# Voltage_Regulator.net
KiCad netlist of a schematic drawn in Altium Designer
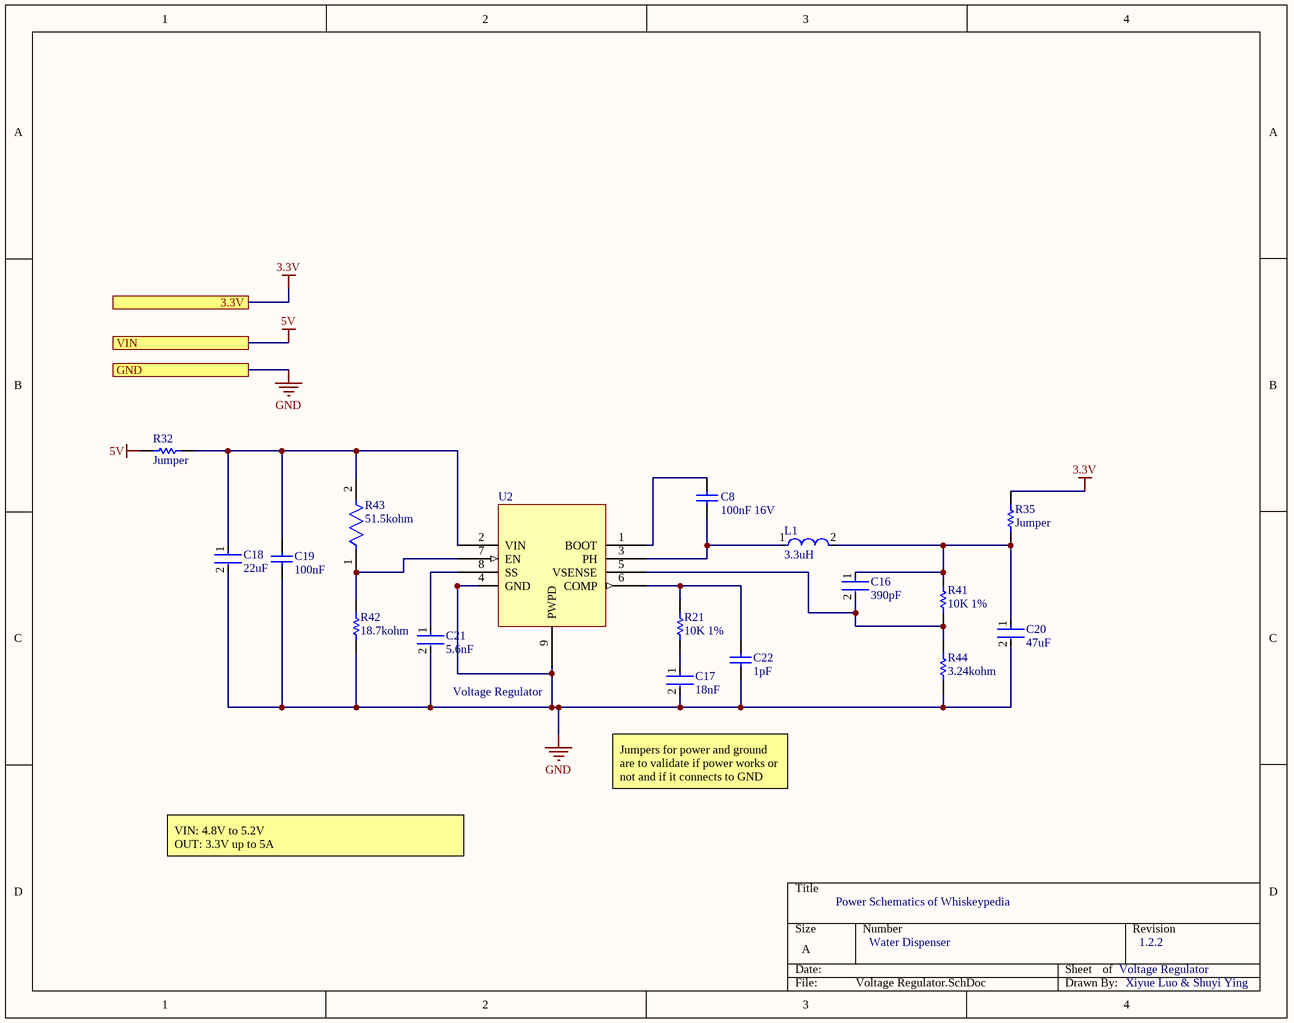
[diagram p0: Voltage Regulator.SchDoc]

(export (version "E")
  (design (tool "Eeschema 10.0.6"))
  (components
    (comp (ref "C8")
      (value "100nF 16V")
      (footprint "CAPC0603(1608)100_N")
      (description "CAP 100nF 16V ±10% 0603 (1608 Metric) Thickness 1mm SMD")
      (fields (field (name "TOLERANCE") "Â±10%"))
      (libsource (lib "Altium Content Vault") (part "CAP"))
    )
    (comp (ref "C16")
      (value "390pF")
      (footprint "FP-CC0603-DA-MFG")
      (description "CAP CER 390PF 50V X7R 0603")
      (fields
        (field (name "OCTOPART") "https://octopart.com/cc0603krx7r9bb391-yageo-39467837")
        (field (name "MANUFACTURER") "YAGEO")
      )
      (libsource (lib "Altium Content Vault") (part "11868f565c42a9108669ba33697ecf6"))
    )
    (comp (ref "C17")
      (value "18nF")
      (footprint "FP-GRM21B-0_1-IPC_A")
      (description "Chip Multilayer Ceramic Capacitors for General Purpose, 0805, 18000pF, C0G, 30ppm/°C, 5%, 50V")
      (fields (field (name "TOLERANCE") "5%"))
      (libsource (lib "Altium Content Vault") (part "b4654b650e69147ec39a6b967a45e02"))
    )
    (comp (ref "C18")
      (value "22uF")
      (footprint "FP-GRM21B-0_2-e0_2_0_7-IPC_C")
      (description "Chip Multilayer Ceramic Capacitors for General Purpose, 0805, 22uF, X5R, 15%, 20%, 10V")
      (fields (field (name "TOLERANCE") "20%") (field (name "VOLTAGE") "10V"))
      (libsource (lib "Altium Content Vault") (part "b4654b650e69147ec39a6b967a45e02"))
    )
    (comp (ref "C19")
      (value "100nF")
      (footprint "CAPC1005X55X25NL05T10")
      (fields (field (name "PART NUMBER") "GRM155R70J104KA01D") (field (name "MANUFACTURER") "Murata"))
      (libsource (lib "Altium Content Vault") (part "CAP"))
    )
    (comp (ref "C20")
      (value "47uF")
      (footprint "FP-GRM31C-0_2-e0_3_0_8-IPC_C")
      (description "Chip Multilayer Ceramic Capacitors for General Purpose, 1206, 47uF, X5R, 15%, 20%, 6.3V")
      (fields (field (name "TOLERANCE") "20%") (field (name "VOLTAGE") "6.3V"))
      (libsource (lib "Altium Content Vault") (part "02cd4be3c70576c341d710602a673aa"))
    )
    (comp (ref "C21")
      (value "5.6nF")
      (footprint "FP-CGA4J-IPC_B")
      (description "Cap Ceramic 5.6nF 50V C0G 5% Pad SMD 0805 +125°C Automotive T/R")
      (fields (field (name "TOLERANCE") "5%"))
      (libsource (lib "Altium Content Vault") (part "b4654b650e69147ec39a6b967a45e02"))
    )
    (comp (ref "C22")
      (value "1pF")
      (footprint "CAPC1005X55X25NL05T10")
      (fields (field (name "PART NUMBER") "GRM1555C1H1R0CA01D") (field (name "MANUFACTURER") "Murata"))
      (libsource (lib "Altium Content Vault") (part "CAP"))
    )
    (comp (ref "L1")
      (value "3.3uH")
      (footprint "FP-SRN8040-MFG")
      (description "FIXED IND 3.3UH 5.6A 21 MOHM SMD")
      (fields (field (name "TOLERANCE") "30%"))
      (libsource (lib "Altium Content Vault") (part "725321dda6339637d4d059423bc1c3c"))
    )
    (comp (ref "R21")
      (value "10K 1%")
      (footprint "RESC0603(1608)_N")
      (description "10K 0.1W 1% 0603 (1608 Metric)  SMD")
      (fields (field (name "POWER") "0.1 W") (field (name "TOLERANCE") "1 %"))
      (libsource (lib "Altium Content Vault") (part "RES"))
    )
    (comp (ref "R32")
      (value "Jumper")
      (footprint "RESC0805(2012)_N")
      (description "Jumper 0805 (2012 Metric)")
      (fields (field (name "TOLERANCE") "None"))
      (libsource (lib "Altium Content Vault") (part "RES"))
    )
    (comp (ref "R35")
      (value "Jumper")
      (footprint "RESC0805(2012)_N")
      (description "Jumper 0805 (2012 Metric)")
      (fields (field (name "TOLERANCE") "None"))
      (libsource (lib "Altium Content Vault") (part "RES"))
    )
    (comp (ref "R41")
      (value "10K 1%")
      (footprint "RESC0603(1608)_N")
      (description "10K 0.1W 1% 0603 (1608 Metric)  SMD")
      (fields (field (name "POWER") "0.1 W") (field (name "TOLERANCE") "1 %"))
      (libsource (lib "Altium Content Vault") (part "RES"))
    )
    (comp (ref "R42")
      (value "18.7kohm")
      (footprint "RESC1608X55X30LL15T15")
      (fields (field (name "PART NUMBER") "ERJ-3EKF1872V") (field (name "MANUFACTURER") "Panasonic"))
      (libsource (lib "Altium Content Vault") (part "RES"))
    )
    (comp (ref "R43")
      (value "51.5kohm")
      (footprint "FP-CRCW0603-HPe3-IPC_B")
      (description "RES Thick Film, 51.1kΩ, 1%, 0.33W, 100ppm/°C, 0603")
      (fields (field (name "TOLERANCE") "1%"))
      (libsource (lib "Altium Content Vault") (part "1029c3af85768c4190bb7ad29bc67b5"))
    )
    (comp (ref "R44")
      (value "3.24kohm")
      (footprint "RESC1608X55X30ML15T15")
      (fields (field (name "PART NUMBER") "ERJ-3EKF3241V") (field (name "MANUFACTURER") "Panasonic"))
      (libsource (lib "Altium Content Vault") (part "RES"))
    )
    (comp (ref "U2")
      (value "Voltage Regulator")
      (footprint "TPS5432DDAR")
      (description "TPS5432 2.95V to 6V Input, 3A Sy")
      (fields
        (field (name "MANUFACTURER") "Texas Instruments")
        (field (name "MANUFACTURER PART NUMBER") "TPS5432DDAR")
      )
      (libsource (lib "Whiskeypedia_Components_SchLib") (part "TPS5432DDAR"))
    )
  )
  (nets
    (net (code "1") (name "3.3V") (class "Default")
      (node (ref "R35") (pin "2") (pinfunction "2_2") (pintype "passive"))
    )
    (net (code "2") (name "5V") (class "Default")
      (node (ref "R32") (pin "1") (pinfunction "1_1") (pintype "passive"))
    )
    (net (code "3") (name "GND") (class "Default")
      (node (ref "C17") (pin "2") (pinfunction "2_2") (pintype "passive"))
      (node (ref "C18") (pin "2") (pinfunction "2_2") (pintype "passive"))
      (node (ref "C19") (pin "1") (pinfunction "1_1") (pintype "passive"))
      (node (ref "C20") (pin "2") (pinfunction "2_2") (pintype "passive"))
      (node (ref "C21") (pin "2") (pinfunction "2_2") (pintype "passive"))
      (node (ref "C22") (pin "1") (pinfunction "1_1") (pintype "passive"))
      (node (ref "R42") (pin "1") (pinfunction "1_1") (pintype "passive"))
      (node (ref "R44") (pin "1") (pinfunction "1_1") (pintype "passive"))
      (node (ref "U2") (pin "4") (pinfunction "GND_4") (pintype "power_in"))
      (node (ref "U2") (pin "9") (pinfunction "PWPD_9") (pintype "passive"))
    )
    (net (code "4") (name "Net-(C16-Pad1)") (class "Default")
      (node (ref "C16") (pin "1") (pinfunction "1_1") (pintype "passive"))
      (node (ref "C20") (pin "1") (pinfunction "1_1") (pintype "passive"))
      (node (ref "L1") (pin "2") (pinfunction "2_2") (pintype "passive"))
      (node (ref "R35") (pin "1") (pinfunction "1_1") (pintype "passive"))
      (node (ref "R41") (pin "2") (pinfunction "2_2") (pintype "passive"))
    )
    (net (code "5") (name "Net-(C17-Pad1)") (class "Default")
      (node (ref "C17") (pin "1") (pinfunction "1_1") (pintype "passive"))
      (node (ref "R21") (pin "1") (pinfunction "1_1") (pintype "passive"))
    )
    (net (code "6") (name "Net-(U2-BOOT)") (class "Default")
      (node (ref "C8") (pin "2") (pinfunction "2_2") (pintype "passive"))
      (node (ref "U2") (pin "1") (pinfunction "BOOT_1") (pintype "passive"))
    )
    (net (code "7") (name "Net-(U2-COMP)") (class "Default")
      (node (ref "C22") (pin "2") (pinfunction "2_2") (pintype "passive"))
      (node (ref "R21") (pin "2") (pinfunction "2_2") (pintype "passive"))
      (node (ref "U2") (pin "6") (pinfunction "COMP_6") (pintype "output"))
    )
    (net (code "8") (name "Net-(U2-EN)") (class "Default")
      (node (ref "R42") (pin "2") (pinfunction "2_2") (pintype "passive"))
      (node (ref "R43") (pin "1") (pinfunction "1_1") (pintype "passive"))
      (node (ref "U2") (pin "7") (pinfunction "EN_7") (pintype "input"))
    )
    (net (code "9") (name "Net-(U2-PH)") (class "Default")
      (node (ref "C8") (pin "1") (pinfunction "1_1") (pintype "passive"))
      (node (ref "L1") (pin "1") (pinfunction "1_1") (pintype "passive"))
      (node (ref "U2") (pin "3") (pinfunction "PH_3") (pintype "passive"))
    )
    (net (code "10") (name "Net-(U2-SS)") (class "Default")
      (node (ref "C21") (pin "1") (pinfunction "1_1") (pintype "passive"))
      (node (ref "U2") (pin "8") (pinfunction "SS_8") (pintype "passive"))
    )
    (net (code "11") (name "Net-(U2-VIN)") (class "Default")
      (node (ref "C18") (pin "1") (pinfunction "1_1") (pintype "passive"))
      (node (ref "C19") (pin "2") (pinfunction "2_2") (pintype "passive"))
      (node (ref "R32") (pin "2") (pinfunction "2_2") (pintype "passive"))
      (node (ref "R43") (pin "2") (pinfunction "2_2") (pintype "passive"))
      (node (ref "U2") (pin "2") (pinfunction "VIN_2") (pintype "power_in"))
    )
    (net (code "12") (name "Net-(U2-VSENSE)") (class "Default")
      (node (ref "C16") (pin "2") (pinfunction "2_2") (pintype "passive"))
      (node (ref "R41") (pin "1") (pinfunction "1_1") (pintype "passive"))
      (node (ref "R44") (pin "2") (pinfunction "2_2") (pintype "passive"))
      (node (ref "U2") (pin "5") (pinfunction "VSENSE_5") (pintype "power_in"))
    )
  )
)
